# ISO.net
KiCad netlist of a schematic drawn in Altium Designer
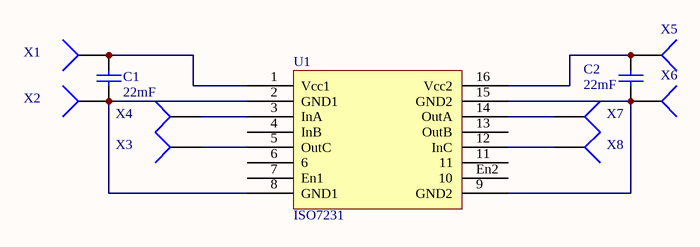
[diagram p0: ISO.SchDoc]

(export (version "E")
  (design (tool "Eeschema 10.0.6"))
  (components
    (comp (ref "C1")
      (value "22mF")
      (footprint "C3216-1206")
      (description "Capacitor (Semiconductor SIM Model)")
      (fields (field (name "MANUFACTURER") "Generic Components") (field (name "PUBLISHER") "Altium Limited"))
      (libsource (lib "Miscellaneous Devices") (part "Cap Semi"))
    )
    (comp (ref "C2")
      (value "22mF")
      (footprint "C3216-1206")
      (description "Capacitor (Semiconductor SIM Model)")
      (fields (field (name "MANUFACTURER") "Generic Components") (field (name "PUBLISHER") "Altium Limited"))
      (libsource (lib "Miscellaneous Devices") (part "Cap Semi"))
    )
    (comp (ref "U1") (value "ISO7231") (footprint "SO-G16/D10.4") (libsource (lib "PAL") (part "ISO7231")))
    (comp (ref "X1")
      (value "~")
      (footprint "PIN1")
      (description "Socket")
      (fields (field (name "MANUFACTURER") "Generic Components") (field (name "PUBLISHER") "Altium Limited"))
      (libsource (lib "Miscellaneous Connectors") (part "Socket"))
    )
    (comp (ref "X2")
      (value "~")
      (footprint "PIN1")
      (description "Socket")
      (fields (field (name "MANUFACTURER") "Generic Components") (field (name "PUBLISHER") "Altium Limited"))
      (libsource (lib "Miscellaneous Connectors") (part "Socket"))
    )
    (comp (ref "X3")
      (value "~")
      (footprint "PIN1")
      (description "Socket")
      (fields (field (name "MANUFACTURER") "Generic Components") (field (name "PUBLISHER") "Altium Limited"))
      (libsource (lib "Miscellaneous Connectors") (part "Socket"))
    )
    (comp (ref "X4")
      (value "~")
      (footprint "PIN1")
      (description "Socket")
      (fields (field (name "MANUFACTURER") "Generic Components") (field (name "PUBLISHER") "Altium Limited"))
      (libsource (lib "Miscellaneous Connectors") (part "Socket"))
    )
    (comp (ref "X5")
      (value "~")
      (footprint "PIN1")
      (description "Socket")
      (fields (field (name "MANUFACTURER") "Generic Components") (field (name "PUBLISHER") "Altium Limited"))
      (libsource (lib "Miscellaneous Connectors") (part "Socket"))
    )
    (comp (ref "X6")
      (value "~")
      (footprint "PIN1")
      (description "Socket")
      (fields (field (name "MANUFACTURER") "Generic Components") (field (name "PUBLISHER") "Altium Limited"))
      (libsource (lib "Miscellaneous Connectors") (part "Socket"))
    )
    (comp (ref "X7")
      (value "~")
      (footprint "PIN1")
      (description "Socket")
      (fields (field (name "MANUFACTURER") "Generic Components") (field (name "PUBLISHER") "Altium Limited"))
      (libsource (lib "Miscellaneous Connectors") (part "Socket"))
    )
    (comp (ref "X8")
      (value "~")
      (footprint "PIN1")
      (description "Socket")
      (fields (field (name "MANUFACTURER") "Generic Components") (field (name "PUBLISHER") "Altium Limited"))
      (libsource (lib "Miscellaneous Connectors") (part "Socket"))
    )
  )
  (nets
    (net (code "1") (name "Net-(C1-Pad1)") (class "Default")
      (node (ref "C1") (pin "1") (pinfunction "1_1") (pintype "passive"))
      (node (ref "U1") (pin "2") (pinfunction "GND1_2") (pintype "passive"))
      (node (ref "U1") (pin "8") (pinfunction "GND1_8") (pintype "passive"))
      (node (ref "X2") (pin "1") (pinfunction "1_1") (pintype "passive"))
    )
    (net (code "2") (name "Net-(C2-Pad1)") (class "Default")
      (node (ref "C2") (pin "1") (pinfunction "1_1") (pintype "passive"))
      (node (ref "U1") (pin "15") (pinfunction "GND2_15") (pintype "passive"))
      (node (ref "U1") (pin "9") (pinfunction "GND2_9") (pintype "passive"))
      (node (ref "X6") (pin "1") (pinfunction "1_1") (pintype "passive"))
    )
    (net (code "3") (name "Net-(U1-InA)") (class "Default")
      (node (ref "U1") (pin "3") (pinfunction "InA_3") (pintype "passive"))
      (node (ref "X4") (pin "1") (pinfunction "1_1") (pintype "passive"))
    )
    (net (code "4") (name "Net-(U1-InC)") (class "Default")
      (node (ref "U1") (pin "12") (pinfunction "InC_12") (pintype "passive"))
      (node (ref "X8") (pin "1") (pinfunction "1_1") (pintype "passive"))
    )
    (net (code "5") (name "Net-(U1-OutA)") (class "Default")
      (node (ref "U1") (pin "14") (pinfunction "OutA_14") (pintype "passive"))
      (node (ref "X7") (pin "1") (pinfunction "1_1") (pintype "passive"))
    )
    (net (code "6") (name "Net-(U1-OutC)") (class "Default")
      (node (ref "U1") (pin "5") (pinfunction "OutC_5") (pintype "passive"))
      (node (ref "X3") (pin "1") (pinfunction "1_1") (pintype "passive"))
    )
    (net (code "7") (name "Net-(U1-Vcc1)") (class "Default")
      (node (ref "C1") (pin "2") (pinfunction "2_2") (pintype "passive"))
      (node (ref "U1") (pin "1") (pinfunction "Vcc1_1") (pintype "passive"))
      (node (ref "X1") (pin "1") (pinfunction "1_1") (pintype "passive"))
    )
    (net (code "8") (name "Net-(U1-Vcc2)") (class "Default")
      (node (ref "C2") (pin "2") (pinfunction "2_2") (pintype "passive"))
      (node (ref "U1") (pin "16") (pinfunction "Vcc2_16") (pintype "passive"))
      (node (ref "X5") (pin "1") (pinfunction "1_1") (pintype "passive"))
    )
    (net (code "9") (name "unconnected-(U1-10-PadEn2)") (class "Default")
      (node (ref "U1") (pin "En2") (pinfunction "10_En2") (pintype "passive"))
    )
    (net (code "10") (name "unconnected-(U1-En1-Pad7)") (class "Default")
      (node (ref "U1") (pin "7") (pinfunction "En1_7") (pintype "passive"))
    )
    (net (code "11") (name "unconnected-(U1-InB-Pad4)") (class "Default")
      (node (ref "U1") (pin "4") (pinfunction "InB_4") (pintype "passive"))
    )
    (net (code "12") (name "unconnected-(U1-OutB-Pad13)") (class "Default")
      (node (ref "U1") (pin "13") (pinfunction "OutB_13") (pintype "passive"))
    )
    (net (code "13") (name "unconnected-(U1-Pad6)") (class "Default")
      (node (ref "U1") (pin "6") (pinfunction "6_6") (pintype "passive"))
    )
    (net (code "14") (name "unconnected-(U1-Pad11)") (class "Default")
      (node (ref "U1") (pin "11") (pinfunction "11_11") (pintype "passive"))
    )
  )
)
